# VistaAir.net
KiCad netlist of a schematic drawn in EAGLE
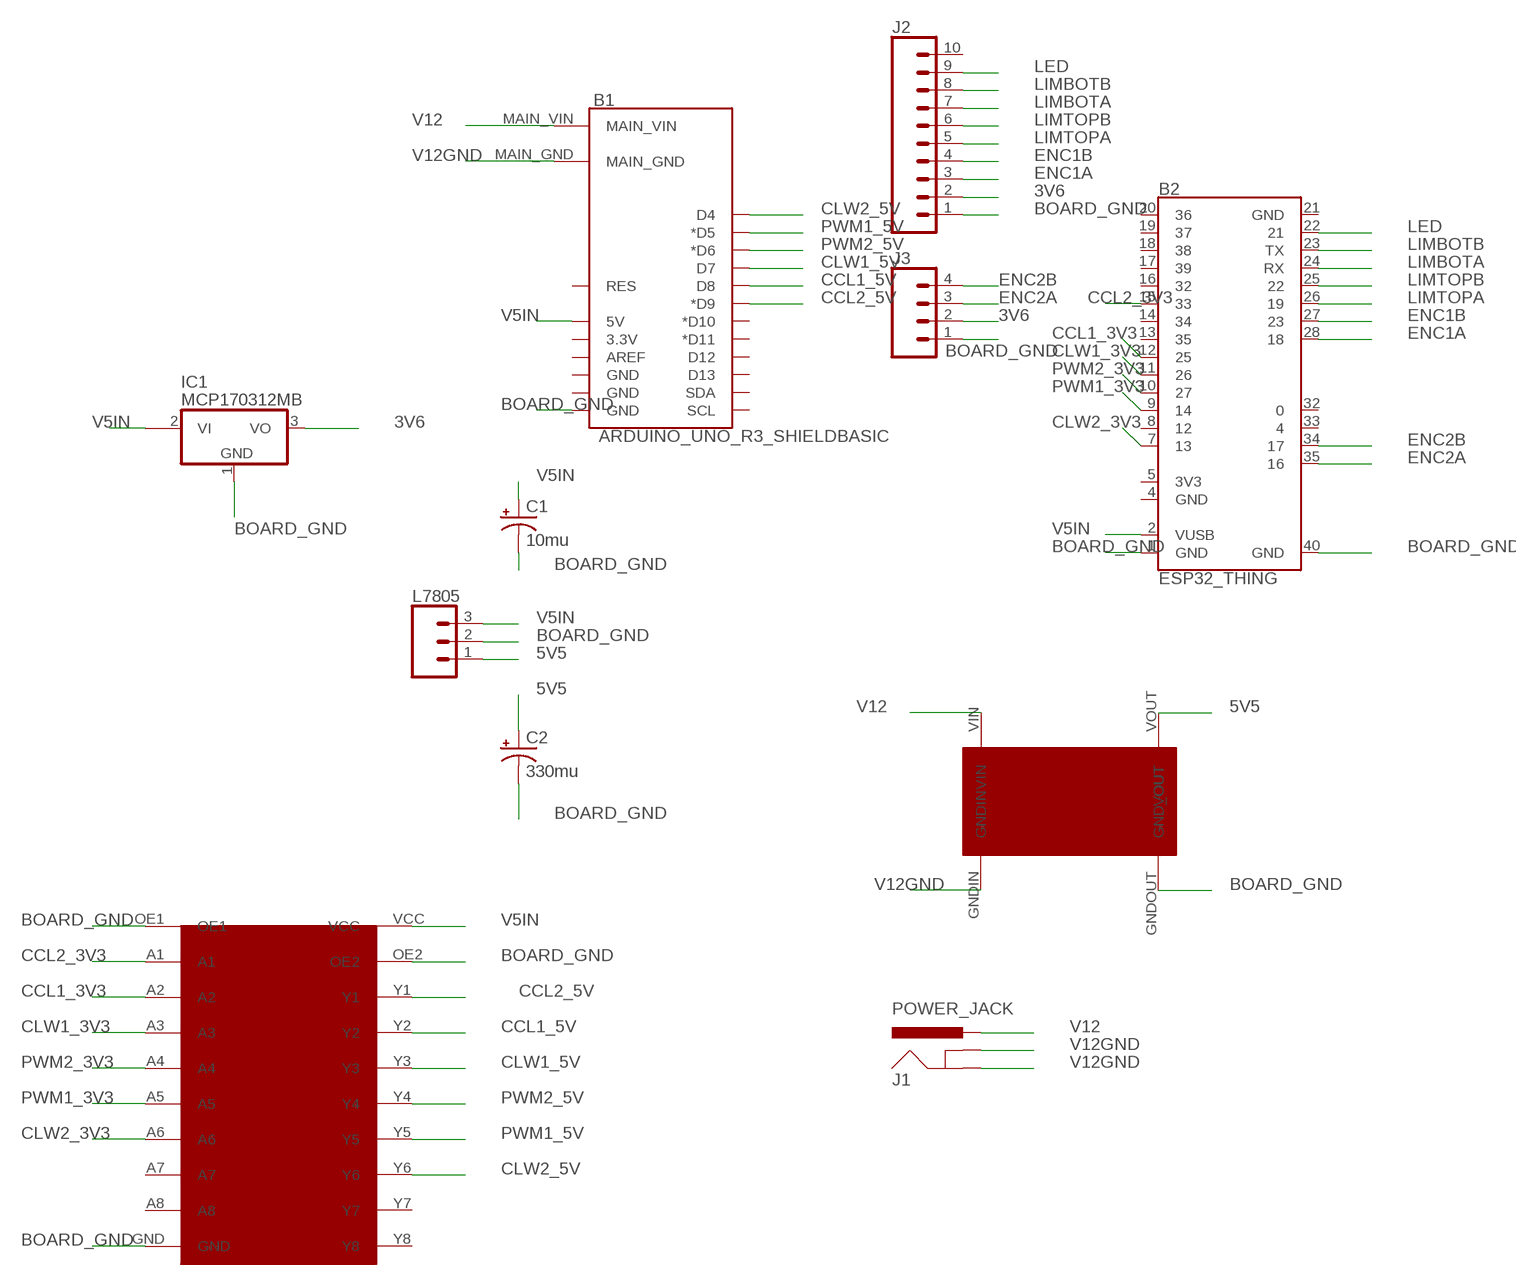
[diagram p0: schematic, sheet 1]

(export (version "E")
  (design (tool "Eeschema 10.0.6"))
  (components
    (comp (ref "B1")
      (value "ARDUINO_UNO_R3_SHIELDBASIC")
      (footprint "eagle-import:UNO_R3_SHIELD")
      (libsource (lib "eagle-import") (part "ARDUINO_UNO_R3_SHIELDBASIC"))
    )
    (comp (ref "B2")
      (value "ESP32_THING")
      (footprint "eagle-import:ESP32_THING")
      (libsource (lib "eagle-import") (part "ESP32_THING"))
    )
    (comp (ref "C1")
      (value "10mu")
      (footprint "eagle-import:TT2D5")
      (libsource (lib "eagle-import") (part "CPOL-USTT2D5"))
    )
    (comp (ref "C2")
      (value "330mu")
      (footprint "eagle-import:TT5D10")
      (libsource (lib "eagle-import") (part "CPOL-USTT5D10"))
    )
    (comp (ref "IC1")
      (value "MCP170312MB")
      (footprint "eagle-import:SOT89")
      (libsource (lib "eagle-import") (part "MCP1703MB12"))
    )
    (comp (ref "J1")
      (value "POWER_JACK")
      (footprint "eagle-import:POWER_JACK_PTH")
      (libsource (lib "eagle-import") (part "POWER_JACK"))
    )
    (comp (ref "J2")
      (value "CONN_10\"")
      (footprint "eagle-import:1X10")
      (libsource (lib "eagle-import") (part "CONN_10{dblquote}"))
    )
    (comp (ref "J3")
      (value "CONN_04")
      (footprint "eagle-import:1X04")
      (libsource (lib "eagle-import") (part "CONN_04"))
    )
    (comp (ref "L7805")
      (value "CONN_03")
      (footprint "eagle-import:1X03")
      (libsource (lib "eagle-import") (part "CONN_03"))
    )
    (comp (ref "U$1")
      (value "SN74AHCT541_SOIC-20")
      (footprint "eagle-import:SN74AHCT541")
      (libsource (lib "eagle-import") (part "SN74AHCT541_SOIC-20"))
    )
    (comp (ref "U$2")
      (value "LM2596_STEPDOWN_MODULE")
      (footprint "eagle-import:LM2596_STEPDOWN_MODULE")
      (libsource (lib "eagle-import") (part "LM2596_STEPDOWN_MODULE"))
    )
  )
  (nets
    (net (code "1") (name "/3V6") (class "Default")
      (node (ref "IC1") (pin "3") (pinfunction "VO_3") (pintype "passive"))
      (node (ref "J2") (pin "2") (pinfunction "2_2") (pintype "passive"))
      (node (ref "J3") (pin "2") (pinfunction "2_2") (pintype "passive"))
    )
    (net (code "2") (name "/5V5") (class "Default")
      (node (ref "C2") (pin "+") (pinfunction "+_+") (pintype "passive"))
      (node (ref "L7805") (pin "1") (pinfunction "1_1") (pintype "passive"))
      (node (ref "U$2") (pin "VOUT") (pinfunction "VOUT_VOUT") (pintype "bidirectional"))
    )
    (net (code "3") (name "/BOARD_GND") (class "Default")
      (node (ref "B1") (pin "BOARD_GND") (pinfunction "GND_BOARD_GND") (pintype "bidirectional"))
      (node (ref "B2") (pin "1") (pinfunction "GND_1") (pintype "bidirectional"))
      (node (ref "B2") (pin "40") (pinfunction "GND_40") (pintype "bidirectional"))
      (node (ref "C1") (pin "-") (pinfunction "-_-") (pintype "passive"))
      (node (ref "C2") (pin "-") (pinfunction "-_-") (pintype "passive"))
      (node (ref "IC1") (pin "1") (pinfunction "GND_1") (pintype "passive"))
      (node (ref "J2") (pin "1") (pinfunction "1_1") (pintype "passive"))
      (node (ref "J3") (pin "1") (pinfunction "1_1") (pintype "passive"))
      (node (ref "L7805") (pin "2") (pinfunction "2_2") (pintype "passive"))
      (node (ref "U$1") (pin "GND") (pinfunction "GND_GND") (pintype "bidirectional"))
      (node (ref "U$1") (pin "OE1") (pinfunction "OE1_OE1") (pintype "bidirectional"))
      (node (ref "U$1") (pin "OE2") (pinfunction "OE2_OE2") (pintype "bidirectional"))
      (node (ref "U$2") (pin "GNDOUT") (pinfunction "GND_OUT_GNDOUT") (pintype "bidirectional"))
    )
    (net (code "4") (name "/CCL1_3V3") (class "Default")
      (node (ref "B2") (pin "12") (pinfunction "25_12") (pintype "bidirectional"))
      (node (ref "U$1") (pin "A2") (pinfunction "A2_A2") (pintype "bidirectional"))
    )
    (net (code "5") (name "/CCL1_5V") (class "Default")
      (node (ref "B1") (pin "D8") (pinfunction "D8_D8") (pintype "bidirectional"))
      (node (ref "U$1") (pin "Y2") (pinfunction "Y2_Y2") (pintype "bidirectional"))
    )
    (net (code "6") (name "/CCL2_3V3") (class "Default")
      (node (ref "B2") (pin "15") (pinfunction "33_15") (pintype "bidirectional"))
      (node (ref "U$1") (pin "A1") (pinfunction "A1_A1") (pintype "bidirectional"))
    )
    (net (code "7") (name "/CCL2_5V") (class "Default")
      (node (ref "B1") (pin "D9") (pinfunction "*D9_D9") (pintype "bidirectional"))
      (node (ref "U$1") (pin "Y1") (pinfunction "Y1_Y1") (pintype "bidirectional"))
    )
    (net (code "8") (name "/CLW1_3V3") (class "Default")
      (node (ref "B2") (pin "11") (pinfunction "26_11") (pintype "bidirectional"))
      (node (ref "U$1") (pin "A3") (pinfunction "A3_A3") (pintype "bidirectional"))
    )
    (net (code "9") (name "/CLW1_5V") (class "Default")
      (node (ref "B1") (pin "D7") (pinfunction "D7_D7") (pintype "bidirectional"))
      (node (ref "U$1") (pin "Y3") (pinfunction "Y3_Y3") (pintype "bidirectional"))
    )
    (net (code "10") (name "/CLW2_3V3") (class "Default")
      (node (ref "B2") (pin "7") (pinfunction "13_7") (pintype "bidirectional"))
      (node (ref "U$1") (pin "A6") (pinfunction "A6_A6") (pintype "bidirectional"))
    )
    (net (code "11") (name "/CLW2_5V") (class "Default")
      (node (ref "B1") (pin "D4") (pinfunction "D4_D4") (pintype "bidirectional"))
      (node (ref "U$1") (pin "Y6") (pinfunction "Y6_Y6") (pintype "bidirectional"))
    )
    (net (code "12") (name "/ENC1A") (class "Default")
      (node (ref "B2") (pin "28") (pinfunction "18_28") (pintype "bidirectional"))
      (node (ref "J2") (pin "3") (pinfunction "3_3") (pintype "passive"))
    )
    (net (code "13") (name "/ENC1B") (class "Default")
      (node (ref "B2") (pin "27") (pinfunction "23_27") (pintype "bidirectional"))
      (node (ref "J2") (pin "4") (pinfunction "4_4") (pintype "passive"))
    )
    (net (code "14") (name "/ENC2A") (class "Default")
      (node (ref "B2") (pin "35") (pinfunction "16_35") (pintype "bidirectional"))
      (node (ref "J3") (pin "3") (pinfunction "3_3") (pintype "passive"))
    )
    (net (code "15") (name "/ENC2B") (class "Default")
      (node (ref "B2") (pin "34") (pinfunction "17_34") (pintype "bidirectional"))
      (node (ref "J3") (pin "4") (pinfunction "4_4") (pintype "passive"))
    )
    (net (code "16") (name "/LED") (class "Default")
      (node (ref "B2") (pin "22") (pinfunction "21_22") (pintype "bidirectional"))
      (node (ref "J2") (pin "9") (pinfunction "9_9") (pintype "passive"))
    )
    (net (code "17") (name "/LIMBOTA") (class "Default")
      (node (ref "B2") (pin "24") (pinfunction "RX_24") (pintype "bidirectional"))
      (node (ref "J2") (pin "7") (pinfunction "7_7") (pintype "passive"))
    )
    (net (code "18") (name "/LIMBOTB") (class "Default")
      (node (ref "B2") (pin "23") (pinfunction "TX_23") (pintype "bidirectional"))
      (node (ref "J2") (pin "8") (pinfunction "8_8") (pintype "passive"))
    )
    (net (code "19") (name "/LIMTOPA") (class "Default")
      (node (ref "B2") (pin "26") (pinfunction "19_26") (pintype "bidirectional"))
      (node (ref "J2") (pin "5") (pinfunction "5_5") (pintype "passive"))
    )
    (net (code "20") (name "/LIMTOPB") (class "Default")
      (node (ref "B2") (pin "25") (pinfunction "22_25") (pintype "bidirectional"))
      (node (ref "J2") (pin "6") (pinfunction "6_6") (pintype "passive"))
    )
    (net (code "21") (name "/PWM1_3V3") (class "Default")
      (node (ref "B2") (pin "9") (pinfunction "14_9") (pintype "bidirectional"))
      (node (ref "U$1") (pin "A5") (pinfunction "A5_A5") (pintype "bidirectional"))
    )
    (net (code "22") (name "/PWM1_5V") (class "Default")
      (node (ref "B1") (pin "D5") (pinfunction "*D5_D5") (pintype "bidirectional"))
      (node (ref "U$1") (pin "Y5") (pinfunction "Y5_Y5") (pintype "bidirectional"))
    )
    (net (code "23") (name "/PWM2_3V3") (class "Default")
      (node (ref "B2") (pin "10") (pinfunction "27_10") (pintype "bidirectional"))
      (node (ref "U$1") (pin "A4") (pinfunction "A4_A4") (pintype "bidirectional"))
    )
    (net (code "24") (name "/PWM2_5V") (class "Default")
      (node (ref "B1") (pin "D6") (pinfunction "*D6_D6") (pintype "bidirectional"))
      (node (ref "U$1") (pin "Y4") (pinfunction "Y4_Y4") (pintype "bidirectional"))
    )
    (net (code "25") (name "/V5IN") (class "Default")
      (node (ref "B1") (pin "5V") (pinfunction "5V_5V") (pintype "bidirectional"))
      (node (ref "B2") (pin "2") (pinfunction "VUSB_2") (pintype "bidirectional"))
      (node (ref "C1") (pin "+") (pinfunction "+_+") (pintype "passive"))
      (node (ref "IC1") (pin "2@1") (pinfunction "VI1_2@1") (pintype "input"))
      (node (ref "L7805") (pin "3") (pinfunction "3_3") (pintype "passive"))
      (node (ref "U$1") (pin "VCC") (pinfunction "VCC_VCC") (pintype "bidirectional"))
    )
    (net (code "26") (name "/V12") (class "Default")
      (node (ref "B1") (pin "MAIN_VIN") (pinfunction "MAIN_VIN_MAIN_VIN") (pintype "bidirectional"))
      (node (ref "J1") (pin "PWR") (pinfunction "PWR_PWR") (pintype "bidirectional"))
      (node (ref "U$2") (pin "VIN") (pinfunction "VIN_VIN") (pintype "bidirectional"))
    )
    (net (code "27") (name "/V12GND") (class "Default")
      (node (ref "B1") (pin "MAIN_GND") (pinfunction "MAIN_GND_MAIN_GND") (pintype "bidirectional"))
      (node (ref "J1") (pin "GND") (pinfunction "GND_GND") (pintype "bidirectional"))
      (node (ref "J1") (pin "GNDBREAK") (pinfunction "GNDBREAK_GNDBREAK") (pintype "bidirectional"))
      (node (ref "U$2") (pin "GNDIN") (pinfunction "GNDIN_GNDIN") (pintype "bidirectional"))
    )
    (net (code "28") (name "unconnected-(B1-*D10-PadD10)") (class "Default")
      (node (ref "B1") (pin "D10") (pinfunction "*D10_D10") (pintype "bidirectional"))
    )
    (net (code "29") (name "unconnected-(B1-*D11-PadD11)") (class "Default")
      (node (ref "B1") (pin "D11") (pinfunction "*D11_D11") (pintype "bidirectional"))
    )
    (net (code "30") (name "unconnected-(B1-GND-Pad5VIN)") (class "Default")
      (node (ref "B1") (pin "5VIN") (pinfunction "GND_5VIN") (pintype "bidirectional"))
    )
    (net (code "31") (name "unconnected-(B1-GND-PadGND@2)") (class "Default")
      (node (ref "B1") (pin "GND@2") (pinfunction "GND_GND@2") (pintype "bidirectional"))
    )
    (net (code "32") (name "unconnected-(B1-Pad3.3V)") (class "Default")
      (node (ref "B1") (pin "3.3V") (pinfunction "3.3V_3.3V") (pintype "bidirectional"))
    )
    (net (code "33") (name "unconnected-(B1-PadAREF)") (class "Default")
      (node (ref "B1") (pin "AREF") (pinfunction "AREF_AREF") (pintype "bidirectional"))
    )
    (net (code "34") (name "unconnected-(B1-PadD12)") (class "Default")
      (node (ref "B1") (pin "D12") (pinfunction "D12_D12") (pintype "bidirectional"))
    )
    (net (code "35") (name "unconnected-(B1-PadD13)") (class "Default")
      (node (ref "B1") (pin "D13") (pinfunction "D13_D13") (pintype "bidirectional"))
    )
    (net (code "36") (name "unconnected-(B1-PadRES)") (class "Default")
      (node (ref "B1") (pin "RES") (pinfunction "RES_RES") (pintype "bidirectional"))
    )
    (net (code "37") (name "unconnected-(B1-PadSCL)") (class "Default")
      (node (ref "B1") (pin "SCL") (pinfunction "SCL_SCL") (pintype "bidirectional"))
    )
    (net (code "38") (name "unconnected-(B1-PadSDA)") (class "Default")
      (node (ref "B1") (pin "SDA") (pinfunction "SDA_SDA") (pintype "bidirectional"))
    )
    (net (code "39") (name "unconnected-(B2-0-Pad32)") (class "Default")
      (node (ref "B2") (pin "32") (pinfunction "0_32") (pintype "bidirectional"))
    )
    (net (code "40") (name "unconnected-(B2-3V3-Pad5)") (class "Default")
      (node (ref "B2") (pin "5") (pinfunction "3V3_5") (pintype "bidirectional"))
    )
    (net (code "41") (name "unconnected-(B2-4-Pad33)") (class "Default")
      (node (ref "B2") (pin "33") (pinfunction "4_33") (pintype "bidirectional"))
    )
    (net (code "42") (name "unconnected-(B2-12-Pad8)") (class "Default")
      (node (ref "B2") (pin "8") (pinfunction "12_8") (pintype "bidirectional"))
    )
    (net (code "43") (name "unconnected-(B2-32-Pad16)") (class "Default")
      (node (ref "B2") (pin "16") (pinfunction "32_16") (pintype "bidirectional"))
    )
    (net (code "44") (name "unconnected-(B2-34-Pad14)") (class "Default")
      (node (ref "B2") (pin "14") (pinfunction "34_14") (pintype "bidirectional"))
    )
    (net (code "45") (name "unconnected-(B2-35-Pad13)") (class "Default")
      (node (ref "B2") (pin "13") (pinfunction "35_13") (pintype "bidirectional"))
    )
    (net (code "46") (name "unconnected-(B2-36-Pad20)") (class "Default")
      (node (ref "B2") (pin "20") (pinfunction "36_20") (pintype "bidirectional"))
    )
    (net (code "47") (name "unconnected-(B2-37-Pad19)") (class "Default")
      (node (ref "B2") (pin "19") (pinfunction "37_19") (pintype "bidirectional"))
    )
    (net (code "48") (name "unconnected-(B2-38-Pad18)") (class "Default")
      (node (ref "B2") (pin "18") (pinfunction "38_18") (pintype "bidirectional"))
    )
    (net (code "49") (name "unconnected-(B2-39-Pad17)") (class "Default")
      (node (ref "B2") (pin "17") (pinfunction "39_17") (pintype "bidirectional"))
    )
    (net (code "50") (name "unconnected-(B2-GND-Pad4)") (class "Default")
      (node (ref "B2") (pin "4") (pinfunction "GND_4") (pintype "bidirectional"))
    )
    (net (code "51") (name "unconnected-(B2-GND-Pad21)") (class "Default")
      (node (ref "B2") (pin "21") (pinfunction "GND_21") (pintype "bidirectional"))
    )
    (net (code "52") (name "unconnected-(IC1-VI-Pad2)") (class "Default")
      (node (ref "IC1") (pin "2") (pinfunction "VI_2") (pintype "input"))
    )
    (net (code "53") (name "unconnected-(J2-Pad10)") (class "Default")
      (node (ref "J2") (pin "10") (pinfunction "10_10") (pintype "passive"))
    )
    (net (code "54") (name "unconnected-(U$1-PadA7)") (class "Default")
      (node (ref "U$1") (pin "A7") (pinfunction "A7_A7") (pintype "bidirectional"))
    )
    (net (code "55") (name "unconnected-(U$1-PadA8)") (class "Default")
      (node (ref "U$1") (pin "A8") (pinfunction "A8_A8") (pintype "bidirectional"))
    )
    (net (code "56") (name "unconnected-(U$1-PadY7)") (class "Default")
      (node (ref "U$1") (pin "Y7") (pinfunction "Y7_Y7") (pintype "bidirectional"))
    )
    (net (code "57") (name "unconnected-(U$1-PadY8)") (class "Default")
      (node (ref "U$1") (pin "Y8") (pinfunction "Y8_Y8") (pintype "bidirectional"))
    )
  )
)
